# llrf_afe_front_panel.net
KiCad netlist of a schematic drawn in Altium Designer
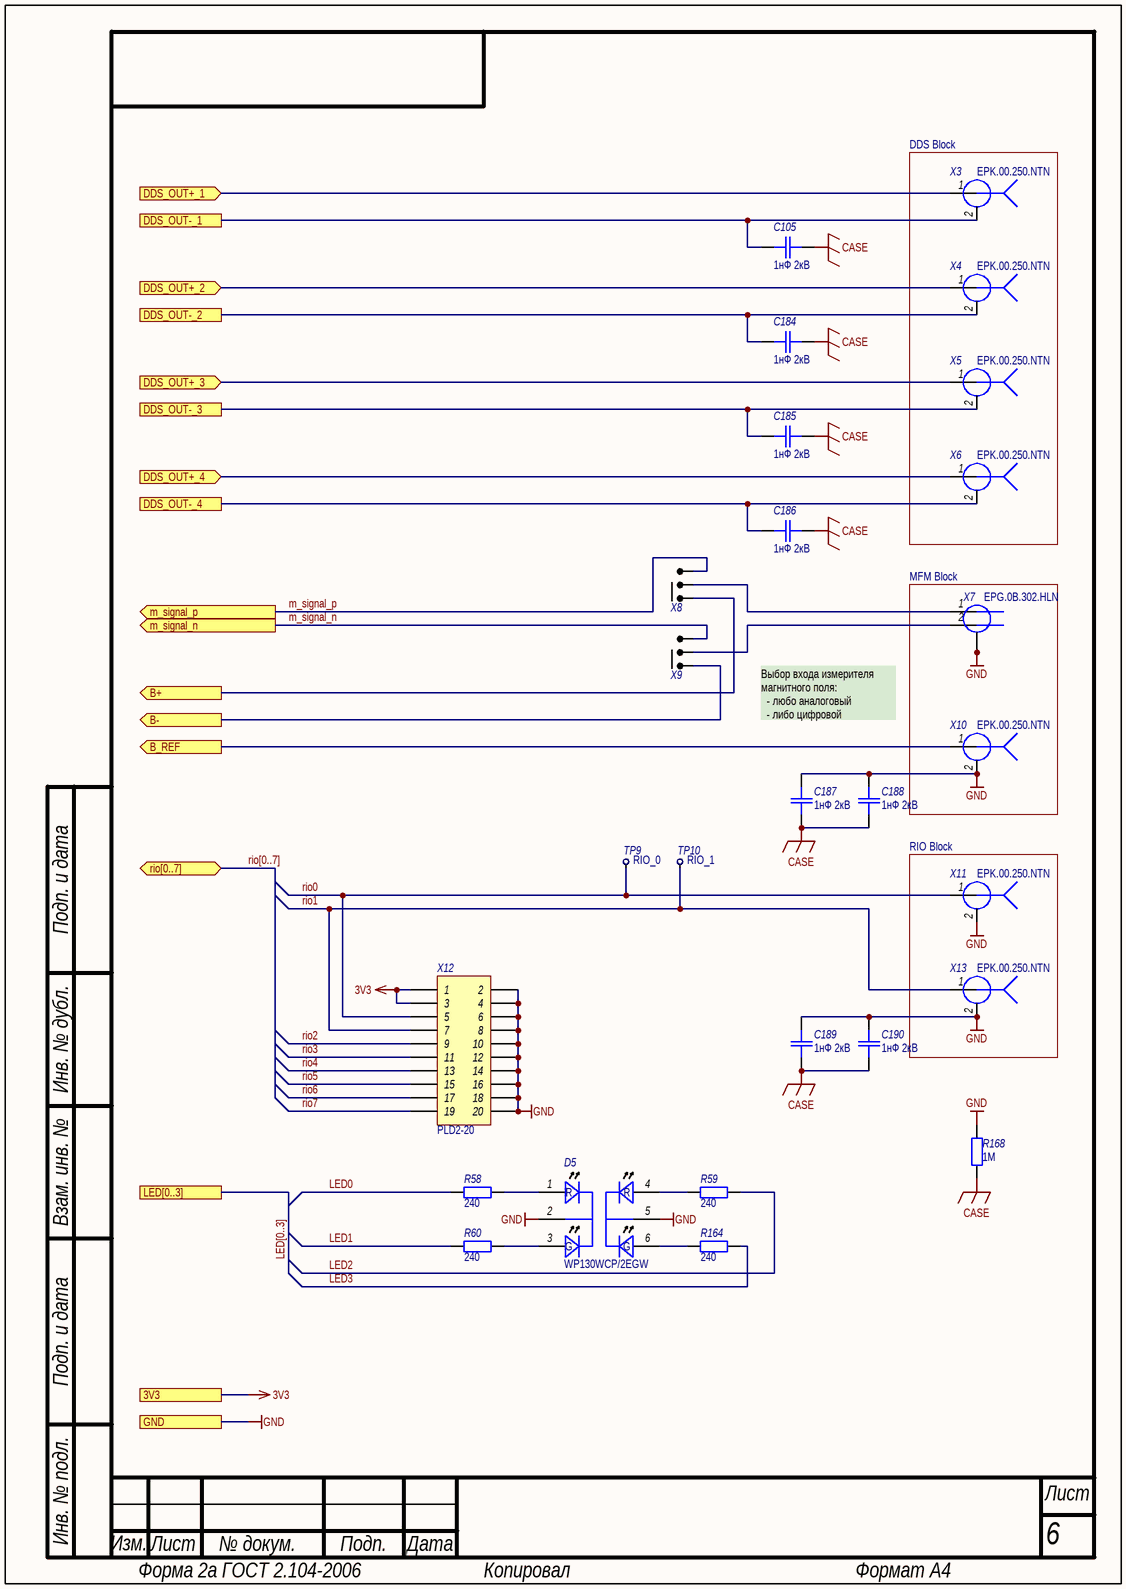
[diagram p0: llrf_afe_front_panel.SchDoc]

(export (version "E")
  (design (tool "Eeschema 10.0.6"))
  (components
    (comp (ref "C105")
      (value "1нФ 2кВ")
      (footprint "SMD_C1206")
      (description "Capacitor")
      (libsource (lib "Passive") (part "Capacitor"))
    )
    (comp (ref "C184")
      (value "1нФ 2кВ")
      (footprint "SMD_C1206")
      (description "Capacitor")
      (libsource (lib "Passive") (part "Capacitor"))
    )
    (comp (ref "C185")
      (value "1нФ 2кВ")
      (footprint "SMD_C1206")
      (description "Capacitor")
      (libsource (lib "Passive") (part "Capacitor"))
    )
    (comp (ref "C186")
      (value "1нФ 2кВ")
      (footprint "SMD_C1206")
      (description "Capacitor")
      (libsource (lib "Passive") (part "Capacitor"))
    )
    (comp (ref "C187")
      (value "1нФ 2кВ")
      (footprint "SMD_C1206")
      (description "Capacitor")
      (libsource (lib "Passive") (part "Capacitor"))
    )
    (comp (ref "C188")
      (value "1нФ 2кВ")
      (footprint "SMD_C1206")
      (description "Capacitor")
      (libsource (lib "Passive") (part "Capacitor"))
    )
    (comp (ref "C189")
      (value "1нФ 2кВ")
      (footprint "SMD_C1206")
      (description "Capacitor")
      (libsource (lib "Passive") (part "Capacitor"))
    )
    (comp (ref "C190")
      (value "1нФ 2кВ")
      (footprint "SMD_C1206")
      (description "Capacitor")
      (libsource (lib "Passive") (part "Capacitor"))
    )
    (comp (ref "D5")
      (value "WP130WCP/2EGW")
      (footprint "WP130WCP")
      (description "2x Bi-Level Circuit Board Indicator")
      (fields (field (name "НАИМЕНОВАНИЕ") "WP130WCP/2EGW"))
      (libsource (lib "Diod") (part "WP130WCP/2EGW"))
    )
    (comp (ref "R58")
      (value "240")
      (footprint "SMD_0603")
      (description "Resistor")
      (libsource (lib "Passive") (part "Resistor"))
    )
    (comp (ref "R59")
      (value "240")
      (footprint "SMD_0603")
      (description "Resistor")
      (libsource (lib "Passive") (part "Resistor"))
    )
    (comp (ref "R60")
      (value "240")
      (footprint "SMD_0603")
      (description "Resistor")
      (libsource (lib "Passive") (part "Resistor"))
    )
    (comp (ref "R164")
      (value "240")
      (footprint "SMD_0603")
      (description "Resistor")
      (libsource (lib "Passive") (part "Resistor"))
    )
    (comp (ref "R168")
      (value "1M")
      (footprint "SMD_1206")
      (description "Resistor")
      (libsource (lib "") (part "Resistor_1"))
    )
    (comp (ref "TP9")
      (value "RIO_0")
      (footprint "TestPoint")
      (fields (field (name "TP_NAME") "RIO_0"))
      (libsource (lib "Connector") (part "TP"))
    )
    (comp (ref "TP10")
      (value "RIO_1")
      (footprint "TestPoint")
      (fields (field (name "TP_NAME") "RIO_1"))
      (libsource (lib "Connector") (part "TP"))
    )
    (comp (ref "X3")
      (value "EPK.00.250.NTN")
      (footprint "EPK.00.250.NTN")
      (fields (field (name "НАИМЕНОВАНИЕ") "EPK.00.250.NTN"))
      (libsource (lib "Connector") (part "EPK.00.250.NTN"))
    )
    (comp (ref "X4")
      (value "EPK.00.250.NTN")
      (footprint "EPK.00.250.NTN")
      (fields (field (name "НАИМЕНОВАНИЕ") "EPK.00.250.NTN"))
      (libsource (lib "Connector") (part "EPK.00.250.NTN"))
    )
    (comp (ref "X5")
      (value "EPK.00.250.NTN")
      (footprint "EPK.00.250.NTN")
      (fields (field (name "НАИМЕНОВАНИЕ") "EPK.00.250.NTN"))
      (libsource (lib "Connector") (part "EPK.00.250.NTN"))
    )
    (comp (ref "X6")
      (value "EPK.00.250.NTN")
      (footprint "EPK.00.250.NTN")
      (fields (field (name "НАИМЕНОВАНИЕ") "EPK.00.250.NTN"))
      (libsource (lib "Connector") (part "EPK.00.250.NTN"))
    )
    (comp (ref "X7")
      (value "EPG.0B.302.HLN")
      (footprint "EPG.0B.302.HLN")
      (fields (field (name "НАИМЕНОВАНИЕ") "EPG.0B.302.HLN"))
      (libsource (lib "Connector") (part "EPG.0B.302.HLN"))
    )
    (comp (ref "X8")
      (value "Jumper 3")
      (footprint "PLS-3")
      (description "Jumper, 3-Pin, Dual row")
      (libsource (lib "Jumper 3") (part "Jumper 3"))
    )
    (comp (ref "X9")
      (value "Jumper 3")
      (footprint "PLS-3")
      (description "Jumper, 3-Pin, Dual row")
      (libsource (lib "Jumper 3") (part "Jumper 3"))
    )
    (comp (ref "X10")
      (value "EPK.00.250.NTN")
      (footprint "EPK.00.250.NTN")
      (fields (field (name "НАИМЕНОВАНИЕ") "EPK.00.250.NTN"))
      (libsource (lib "Connector") (part "EPK.00.250.NTN"))
    )
    (comp (ref "X11")
      (value "EPK.00.250.NTN")
      (footprint "EPK.00.250.NTN")
      (fields (field (name "НАИМЕНОВАНИЕ") "EPK.00.250.NTN"))
      (libsource (lib "Connector") (part "EPK.00.250.NTN"))
    )
    (comp (ref "X12")
      (value "Header 2X20")
      (footprint "PLD2-20")
      (description "Header, 20-Pin, Dual row")
      (fields (field (name "НАИМЕНОВАНИЕ") "PLD2-20"))
      (libsource (lib "Connector") (part "Header 2X20"))
    )
    (comp (ref "X13")
      (value "EPK.00.250.NTN")
      (footprint "EPK.00.250.NTN")
      (fields (field (name "НАИМЕНОВАНИЕ") "EPK.00.250.NTN"))
      (libsource (lib "Connector") (part "EPK.00.250.NTN"))
    )
  )
  (nets
    (net (code "1") (name "/B+") (class "Default")
      (node (ref "X8") (pin "1") (pinfunction "1_1") (pintype "passive"))
    )
    (net (code "2") (name "/B-") (class "Default")
      (node (ref "X9") (pin "1") (pinfunction "1_1") (pintype "passive"))
    )
    (net (code "3") (name "/B_REF") (class "Default")
      (node (ref "X10") (pin "1") (pinfunction "Signal_1") (pintype "passive"))
    )
    (net (code "4") (name "/DDS_OUT+_1") (class "Default")
      (node (ref "X3") (pin "1") (pinfunction "Signal_1") (pintype "passive"))
    )
    (net (code "5") (name "/DDS_OUT+_2") (class "Default")
      (node (ref "X4") (pin "1") (pinfunction "Signal_1") (pintype "passive"))
    )
    (net (code "6") (name "/DDS_OUT+_3") (class "Default")
      (node (ref "X5") (pin "1") (pinfunction "Signal_1") (pintype "passive"))
    )
    (net (code "7") (name "/DDS_OUT+_4") (class "Default")
      (node (ref "X6") (pin "1") (pinfunction "Signal_1") (pintype "passive"))
    )
    (net (code "8") (name "/DDS_OUT-_1") (class "Default")
      (node (ref "C105") (pin "2") (pinfunction "2_2") (pintype "passive"))
      (node (ref "X3") (pin "2") (pinfunction "GND_2") (pintype "passive"))
    )
    (net (code "9") (name "/DDS_OUT-_2") (class "Default")
      (node (ref "C184") (pin "2") (pinfunction "2_2") (pintype "passive"))
      (node (ref "X4") (pin "2") (pinfunction "GND_2") (pintype "passive"))
    )
    (net (code "10") (name "/DDS_OUT-_3") (class "Default")
      (node (ref "C185") (pin "2") (pinfunction "2_2") (pintype "passive"))
      (node (ref "X5") (pin "2") (pinfunction "GND_2") (pintype "passive"))
    )
    (net (code "11") (name "/DDS_OUT-_4") (class "Default")
      (node (ref "C186") (pin "2") (pinfunction "2_2") (pintype "passive"))
      (node (ref "X6") (pin "2") (pinfunction "GND_2") (pintype "passive"))
    )
    (net (code "12") (name "/LED0") (class "Default")
      (node (ref "R58") (pin "1") (pinfunction "1_1") (pintype "passive"))
    )
    (net (code "13") (name "/LED1") (class "Default")
      (node (ref "R60") (pin "1") (pinfunction "1_1") (pintype "passive"))
    )
    (net (code "14") (name "/LED2") (class "Default")
      (node (ref "R59") (pin "2") (pinfunction "2_2") (pintype "passive"))
    )
    (net (code "15") (name "/LED3") (class "Default")
      (node (ref "R164") (pin "2") (pinfunction "2_2") (pintype "passive"))
    )
    (net (code "17") (name "/m_signal_n") (class "Default")
      (node (ref "X9") (pin "3") (pinfunction "3_3") (pintype "passive"))
    )
    (net (code "18") (name "/m_signal_p") (class "Default")
      (node (ref "X8") (pin "3") (pinfunction "3_3") (pintype "passive"))
    )
    (net (code "19") (name "/rio0") (class "Default")
      (node (ref "TP9") (pin "0") (pinfunction "TP_0") (pintype "passive"))
      (node (ref "X11") (pin "1") (pinfunction "Signal_1") (pintype "passive"))
      (node (ref "X12") (pin "5") (pinfunction "5_5") (pintype "passive"))
    )
    (net (code "20") (name "/rio1") (class "Default")
      (node (ref "TP10") (pin "0") (pinfunction "TP_0") (pintype "passive"))
      (node (ref "X12") (pin "7") (pinfunction "7_7") (pintype "passive"))
      (node (ref "X13") (pin "1") (pinfunction "Signal_1") (pintype "passive"))
    )
    (net (code "21") (name "/rio2") (class "Default")
      (node (ref "X12") (pin "9") (pinfunction "9_9") (pintype "passive"))
    )
    (net (code "22") (name "/rio3") (class "Default")
      (node (ref "X12") (pin "11") (pinfunction "11_11") (pintype "passive"))
    )
    (net (code "23") (name "/rio4") (class "Default")
      (node (ref "X12") (pin "13") (pinfunction "13_13") (pintype "passive"))
    )
    (net (code "24") (name "/rio5") (class "Default")
      (node (ref "X12") (pin "15") (pinfunction "15_15") (pintype "passive"))
    )
    (net (code "25") (name "/rio6") (class "Default")
      (node (ref "X12") (pin "17") (pinfunction "17_17") (pintype "passive"))
    )
    (net (code "26") (name "/rio7") (class "Default")
      (node (ref "X12") (pin "19") (pinfunction "19_19") (pintype "passive"))
    )
    (net (code "28") (name "3V3") (class "Default")
      (node (ref "X12") (pin "1") (pinfunction "1_1") (pintype "passive"))
      (node (ref "X12") (pin "3") (pinfunction "3_3") (pintype "passive"))
    )
    (net (code "29") (name "CASE") (class "Default")
      (node (ref "C105") (pin "1") (pinfunction "1_1") (pintype "passive"))
      (node (ref "C184") (pin "1") (pinfunction "1_1") (pintype "passive"))
      (node (ref "C185") (pin "1") (pinfunction "1_1") (pintype "passive"))
      (node (ref "C186") (pin "1") (pinfunction "1_1") (pintype "passive"))
      (node (ref "C187") (pin "1") (pinfunction "1_1") (pintype "passive"))
      (node (ref "C188") (pin "1") (pinfunction "1_1") (pintype "passive"))
      (node (ref "C189") (pin "1") (pinfunction "1_1") (pintype "passive"))
      (node (ref "C190") (pin "1") (pinfunction "1_1") (pintype "passive"))
      (node (ref "R168") (pin "2") (pinfunction "2_2") (pintype "passive"))
    )
    (net (code "30") (name "GND") (class "Default")
      (node (ref "C187") (pin "2") (pinfunction "2_2") (pintype "passive"))
      (node (ref "C188") (pin "2") (pinfunction "2_2") (pintype "passive"))
      (node (ref "C189") (pin "2") (pinfunction "2_2") (pintype "passive"))
      (node (ref "C190") (pin "2") (pinfunction "2_2") (pintype "passive"))
      (node (ref "D5") (pin "2") (pintype "passive"))
      (node (ref "D5") (pin "5") (pintype "passive"))
      (node (ref "R168") (pin "1") (pinfunction "1_1") (pintype "passive"))
      (node (ref "X10") (pin "2") (pinfunction "GND_2") (pintype "passive"))
      (node (ref "X11") (pin "2") (pinfunction "GND_2") (pintype "passive"))
      (node (ref "X12") (pin "10") (pinfunction "10_10") (pintype "passive"))
      (node (ref "X12") (pin "12") (pinfunction "12_12") (pintype "passive"))
      (node (ref "X12") (pin "14") (pinfunction "14_14") (pintype "passive"))
      (node (ref "X12") (pin "16") (pinfunction "16_16") (pintype "passive"))
      (node (ref "X12") (pin "18") (pinfunction "18_18") (pintype "passive"))
      (node (ref "X12") (pin "2") (pinfunction "2_2") (pintype "passive"))
      (node (ref "X12") (pin "20") (pinfunction "20_20") (pintype "passive"))
      (node (ref "X12") (pin "4") (pinfunction "4_4") (pintype "passive"))
      (node (ref "X12") (pin "6") (pinfunction "6_6") (pintype "passive"))
      (node (ref "X12") (pin "8") (pinfunction "8_8") (pintype "passive"))
      (node (ref "X13") (pin "2") (pinfunction "GND_2") (pintype "passive"))
      (node (ref "X7") (pin "4") (pinfunction "GND_4") (pintype "passive"))
      (node (ref "X7") (pin "5") (pinfunction "GND_5") (pintype "passive"))
      (node (ref "X7") (pin "6") (pinfunction "GND_6") (pintype "passive"))
      (node (ref "X7") (pin "7") (pinfunction "GND_7") (pintype "passive"))
    )
    (net (code "31") (name "Net-(D5-Pad1)") (class "Default")
      (node (ref "D5") (pin "1") (pintype "passive"))
      (node (ref "R58") (pin "2") (pinfunction "2_2") (pintype "passive"))
    )
    (net (code "32") (name "Net-(D5-Pad3)") (class "Default")
      (node (ref "D5") (pin "3") (pintype "passive"))
      (node (ref "R60") (pin "2") (pinfunction "2_2") (pintype "passive"))
    )
    (net (code "33") (name "Net-(D5-Pad4)") (class "Default")
      (node (ref "D5") (pin "4") (pintype "passive"))
      (node (ref "R59") (pin "1") (pinfunction "1_1") (pintype "passive"))
    )
    (net (code "34") (name "Net-(D5-Pad6)") (class "Default")
      (node (ref "D5") (pin "6") (pintype "passive"))
      (node (ref "R164") (pin "1") (pinfunction "1_1") (pintype "passive"))
    )
    (net (code "35") (name "Net-(X7-Signal_1)") (class "Default")
      (node (ref "X7") (pin "1") (pinfunction "Signal_1_1") (pintype "passive"))
      (node (ref "X8") (pin "2") (pinfunction "2_2") (pintype "passive"))
    )
    (net (code "36") (name "Net-(X7-Signal_2)") (class "Default")
      (node (ref "X7") (pin "2") (pinfunction "Signal_2_2") (pintype "passive"))
      (node (ref "X9") (pin "2") (pinfunction "2_2") (pintype "passive"))
    )
  )
)
